# SiLPA_HE.net
KiCad netlist of a schematic drawn in Altium Designer
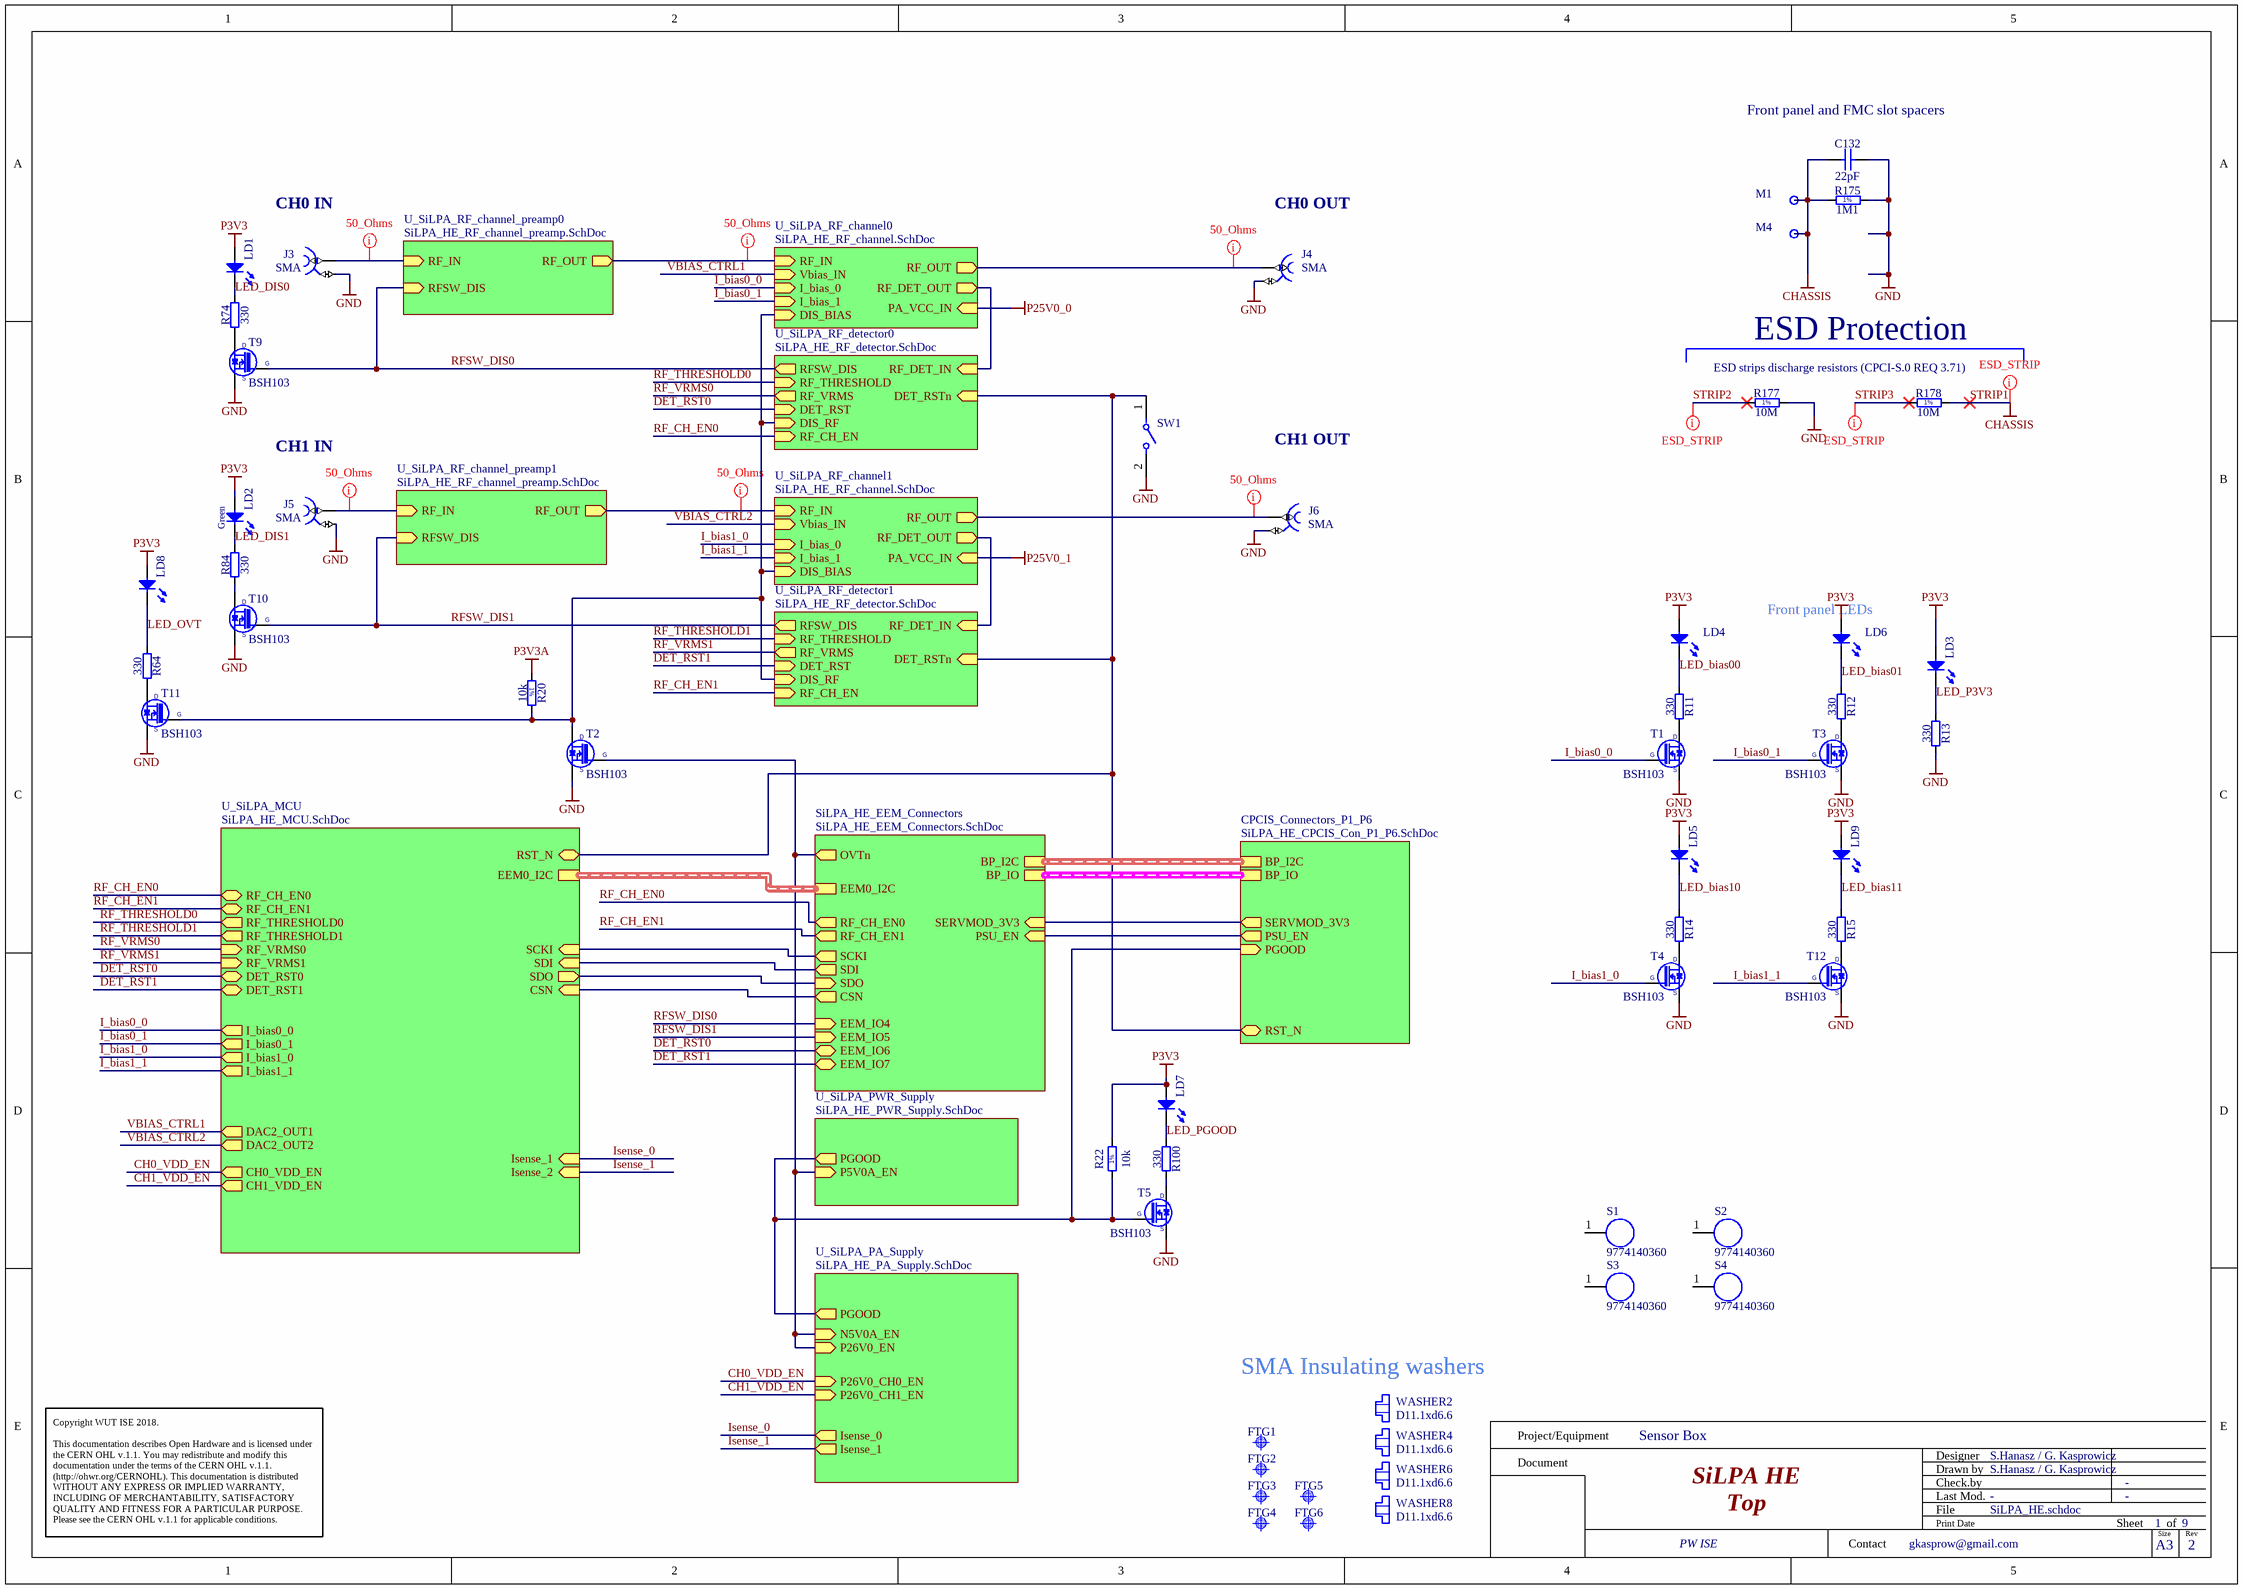
[diagram p0: SiLPA_HE.schdoc]

(export (version "E")
  (design (tool "Eeschema 10.0.6"))
  (components
    (comp (ref "C132")
      (value "22pF")
      (footprint "CAPC1005X55N")
      (description "Non-polarised capacitor")
      (fields
        (field (name "PART NUMBER") "CC0402_22PF_50V_5%_C0G")
        (field (name "VOLTAGE") "50V")
        (field (name "AUTHOR") "CERN DEM JLC")
      )
      (libsource (lib "Capacitors") (part "Capacitor - non polarized"))
    )
    (comp (ref "FTG1")
      (value "Use only in PCB")
      (footprint "FIDUCIAL_TOP_C100-200")
      (description "Fiducial Target")
      (fields (field (name "PART NUMBER") "FIDUCIAL_TARGET_C100-200") (field (name "AUTHOR") "CERN DEM JLC"))
      (libsource (lib "Eletro-mechanical") (part "Fiducial Target"))
    )
    (comp (ref "FTG2")
      (value "Use only in PCB")
      (footprint "FIDUCIAL_TOP_S100-200")
      (description "Fiducial Target")
      (fields (field (name "PART NUMBER") "FIDUCIAL_TARGET_S100-200") (field (name "AUTHOR") "CERN DEM JLC"))
      (libsource (lib "Eletro-mechanical") (part "Fiducial Target"))
    )
    (comp (ref "FTG3")
      (value "Use only in PCB")
      (footprint "FIDUCIAL_TOP_S100-200")
      (description "Fiducial Target")
      (fields (field (name "PART NUMBER") "FIDUCIAL_TARGET_S100-200") (field (name "AUTHOR") "CERN DEM JLC"))
      (libsource (lib "Eletro-mechanical") (part "Fiducial Target"))
    )
    (comp (ref "FTG4")
      (value "Use only in PCB")
      (footprint "FIDUCIAL_TOP_S100-200")
      (description "Fiducial Target")
      (fields (field (name "PART NUMBER") "FIDUCIAL_TARGET_S100-200") (field (name "AUTHOR") "CERN DEM JLC"))
      (libsource (lib "Eletro-mechanical") (part "Fiducial Target"))
    )
    (comp (ref "FTG5")
      (value "Use only in PCB")
      (footprint "FIDUCIAL_TOP_S100-200")
      (description "Fiducial Target")
      (fields (field (name "PART NUMBER") "FIDUCIAL_TARGET_S100-200") (field (name "AUTHOR") "CERN DEM JLC"))
      (libsource (lib "Eletro-mechanical") (part "Fiducial Target"))
    )
    (comp (ref "FTG6")
      (value "Use only in PCB")
      (footprint "FIDUCIAL_TOP_S100-200")
      (description "Fiducial Target")
      (fields (field (name "PART NUMBER") "FIDUCIAL_TARGET_S100-200") (field (name "AUTHOR") "CERN DEM JLC"))
      (libsource (lib "Eletro-mechanical") (part "Fiducial Target"))
    )
    (comp (ref "J3")
      (value "SMA")
      (footprint "SiLPA:DELOCK_65848")
      (description "50 Ohm Through Hole SMA Right Angle PCB Jack")
      (fields
        (field (name "PART NUMBER") "DELOCK_65848")
        (field (name "MANUFACTURER") "DELOCK")
        (field (name "AUTHOR") "GK")
      )
      (libsource (lib "") (part "DELOCK_65848_1"))
    )
    (comp (ref "J4")
      (value "SMA")
      (footprint "SiLPA:DELOCK_65848")
      (description "50 Ohm Through Hole SMA Right Angle PCB Jack")
      (fields
        (field (name "PART NUMBER") "DELOCK_65848")
        (field (name "MANUFACTURER") "DELOCK")
        (field (name "AUTHOR") "GK")
      )
      (libsource (lib "SiLPA") (part "DELOCK_65848"))
    )
    (comp (ref "J5")
      (value "SMA")
      (footprint "SiLPA:DELOCK_65848")
      (description "50 Ohm Through Hole SMA Right Angle PCB Jack")
      (fields
        (field (name "PART NUMBER") "DELOCK_65848")
        (field (name "MANUFACTURER") "DELOCK")
        (field (name "AUTHOR") "GK")
      )
      (libsource (lib "") (part "DELOCK_65848_1"))
    )
    (comp (ref "J6")
      (value "SMA")
      (footprint "SiLPA:DELOCK_65848")
      (description "50 Ohm Through Hole SMA Right Angle PCB Jack")
      (fields
        (field (name "PART NUMBER") "DELOCK_65848")
        (field (name "MANUFACTURER") "DELOCK")
        (field (name "AUTHOR") "GK")
      )
      (libsource (lib "SiLPA") (part "DELOCK_65848"))
    )
    (comp (ref "LD1")
      (value "~")
      (footprint "LED_AVAGO_HSMC-C120")
      (description "LED Red 1C 2A")
      (fields
        (field (name "PART NUMBER") "LED_AVAGO_HSMC-C120")
        (field (name "MANUFACTURER") "AVAGO TECHNOLOGIES")
        (field (name "AUTHOR") "CERN DEM JMW")
      )
      (libsource (lib "SiLPA_own") (part "LED Red 1C 2A"))
    )
    (comp (ref "LD2")
      (value "Green")
      (footprint "LED_AVAGO_HSME-C120")
      (description "LED Green 1C 2A")
      (fields
        (field (name "PART NUMBER") "LED_AVAGO_HSME-C120")
        (field (name "MANUFACTURER") "AVAGO TECHNOLOGIES")
        (field (name "AUTHOR") "CERN DEM JMW")
      )
      (libsource (lib "SiLPA_own") (part "LED_AVAGO_HSME-C120"))
    )
    (comp (ref "LD3")
      (value "~")
      (footprint "LED_AVAGO_HSME-C120")
      (description "LED Green 1C 2A")
      (fields
        (field (name "PART NUMBER") "LED_AVAGO_HSME-C120")
        (field (name "MANUFACTURER") "AVAGO TECHNOLOGIES")
        (field (name "AUTHOR") "CERN DEM JMW")
      )
      (libsource (lib "SiLPA_own") (part "LED Green 1C 2A"))
    )
    (comp (ref "LD4")
      (value "~")
      (footprint "LED_AVAGO_HSME-C120")
      (description "LED Green 1C 2A")
      (fields
        (field (name "PART NUMBER") "LED_AVAGO_HSME-C120")
        (field (name "MANUFACTURER") "AVAGO TECHNOLOGIES")
        (field (name "AUTHOR") "CERN DEM JMW")
      )
      (libsource (lib "SiLPA_own") (part "LED Green 1C 2A"))
    )
    (comp (ref "LD5")
      (value "~")
      (footprint "LED_AVAGO_HSME-C120")
      (description "LED Green 1C 2A")
      (fields
        (field (name "PART NUMBER") "LED_AVAGO_HSME-C120")
        (field (name "MANUFACTURER") "AVAGO TECHNOLOGIES")
        (field (name "AUTHOR") "CERN DEM JMW")
      )
      (libsource (lib "SiLPA_own") (part "LED Green 1C 2A"))
    )
    (comp (ref "LD6")
      (value "~")
      (footprint "LED_AVAGO_HSME-C120")
      (description "LED Green 1C 2A")
      (fields
        (field (name "PART NUMBER") "LED_AVAGO_HSME-C120")
        (field (name "MANUFACTURER") "AVAGO TECHNOLOGIES")
        (field (name "AUTHOR") "CERN DEM JMW")
      )
      (libsource (lib "SiLPA_own") (part "LED Green 1C 2A"))
    )
    (comp (ref "LD7")
      (value "~")
      (footprint "LED_AVAGO_HSME-C120")
      (description "LED Green 1C 2A")
      (fields
        (field (name "PART NUMBER") "LED_AVAGO_HSME-C120")
        (field (name "MANUFACTURER") "AVAGO TECHNOLOGIES")
        (field (name "AUTHOR") "CERN DEM JMW")
      )
      (libsource (lib "SiLPA_own") (part "LED Green 1C 2A"))
    )
    (comp (ref "LD8")
      (value "~")
      (footprint "LED_AVAGO_HSMC-C120")
      (description "LED Red 1C 2A")
      (fields
        (field (name "PART NUMBER") "LED_AVAGO_HSMC-C120")
        (field (name "MANUFACTURER") "AVAGO TECHNOLOGIES")
        (field (name "AUTHOR") "CERN DEM JMW")
      )
      (libsource (lib "SiLPA_own") (part "LED Red 1C 2A"))
    )
    (comp (ref "LD9")
      (value "~")
      (footprint "LED_AVAGO_HSME-C120")
      (description "LED Green 1C 2A")
      (fields
        (field (name "PART NUMBER") "LED_AVAGO_HSME-C120")
        (field (name "MANUFACTURER") "AVAGO TECHNOLOGIES")
        (field (name "AUTHOR") "CERN DEM JMW")
      )
      (libsource (lib "SiLPA_own") (part "LED Green 1C 2A"))
    )
    (comp (ref "M1")
      (value "Plated Hole")
      (footprint "MTG300_600")
      (description "Single Terminal Socket")
      (fields (field (name "PART NUMBER") "PLATED_HOLE3.0_PAD6.0") (field (name "AUTHOR") "CERN DEM JLC"))
      (libsource (lib "Eletro-mechanical") (part "Single Terminal Socket"))
    )
    (comp (ref "M4")
      (value "Plated Hole")
      (footprint "MTG300_600")
      (description "Single Terminal Socket")
      (fields (field (name "PART NUMBER") "PLATED_HOLE3.0_PAD6.0") (field (name "AUTHOR") "CERN DEM JLC"))
      (libsource (lib "Eletro-mechanical") (part "Single Terminal Socket"))
    )
    (comp (ref "R11")
      (value "330")
      (footprint "RESC1005X40N")
      (description "Resistor - 1%")
      (fields
        (field (name "PART NUMBER") "R0402_330R_1%_0.0625W_100PPM")
        (field (name "POWER") "0.0625W")
        (field (name "AUTHOR") "CERN DEM JLC")
      )
      (libsource (lib "Resistors") (part "Resistor - 1%"))
    )
    (comp (ref "R12")
      (value "330")
      (footprint "RESC1005X40N")
      (description "Resistor - 1%")
      (fields
        (field (name "PART NUMBER") "R0402_330R_1%_0.0625W_100PPM")
        (field (name "POWER") "0.0625W")
        (field (name "AUTHOR") "CERN DEM JLC")
      )
      (libsource (lib "Resistors") (part "Resistor - 1%"))
    )
    (comp (ref "R13")
      (value "330")
      (footprint "RESC1005X40N")
      (description "Resistor - 1%")
      (fields
        (field (name "PART NUMBER") "R0402_330R_1%_0.0625W_100PPM")
        (field (name "POWER") "0.0625W")
        (field (name "AUTHOR") "CERN DEM JLC")
      )
      (libsource (lib "Resistors") (part "Resistor - 1%"))
    )
    (comp (ref "R14")
      (value "330")
      (footprint "RESC1005X40N")
      (description "Resistor - 1%")
      (fields
        (field (name "PART NUMBER") "R0402_330R_1%_0.0625W_100PPM")
        (field (name "POWER") "0.0625W")
        (field (name "AUTHOR") "CERN DEM JLC")
      )
      (libsource (lib "Resistors") (part "Resistor - 1%"))
    )
    (comp (ref "R15")
      (value "330")
      (footprint "RESC1005X40N")
      (description "Resistor - 1%")
      (fields
        (field (name "PART NUMBER") "R0402_330R_1%_0.0625W_100PPM")
        (field (name "POWER") "0.0625W")
        (field (name "AUTHOR") "CERN DEM JLC")
      )
      (libsource (lib "Resistors") (part "Resistor - 1%"))
    )
    (comp (ref "R20")
      (value "10k")
      (footprint "RESC1005X40N")
      (description "Resistor - 1%")
      (fields
        (field (name "PART NUMBER") "R0402_10K_1%_0.0625W_100PPM")
        (field (name "POWER") "0.0625W")
        (field (name "AUTHOR") "CERN DEM JLC")
      )
      (libsource (lib "Resistors") (part "Resistor - 1%"))
    )
    (comp (ref "R22")
      (value "10k")
      (footprint "RESC1005X40N")
      (description "Resistor - 1%")
      (fields
        (field (name "PART NUMBER") "R0402_10K_1%_0.0625W_100PPM")
        (field (name "POWER") "0.0625W")
        (field (name "AUTHOR") "CERN DEM JLC")
      )
      (libsource (lib "EEM_FMC_Carrier") (part "R0402_10K_1%_0.0625W_100PPM"))
    )
    (comp (ref "R64")
      (value "330")
      (footprint "RESC1005X40N")
      (description "Resistor - 1%")
      (fields
        (field (name "PART NUMBER") "R0402_330R_1%_0.0625W_100PPM")
        (field (name "POWER") "0.0625W")
        (field (name "AUTHOR") "CERN DEM JLC")
      )
      (libsource (lib "Resistors") (part "Resistor - 1%"))
    )
    (comp (ref "R74")
      (value "330")
      (footprint "RESC1005X40N")
      (description "Resistor - 1%")
      (fields
        (field (name "PART NUMBER") "R0402_330R_1%_0.0625W_100PPM")
        (field (name "POWER") "0.0625W")
        (field (name "AUTHOR") "CERN DEM JLC")
      )
      (libsource (lib "Resistors") (part "Resistor - 1%"))
    )
    (comp (ref "R84")
      (value "330")
      (footprint "RESC1005X40N")
      (description "Resistor - 1%")
      (fields
        (field (name "PART NUMBER") "R0402_330R_1%_0.0625W_100PPM")
        (field (name "POWER") "0.0625W")
        (field (name "AUTHOR") "CERN DEM JLC")
      )
      (libsource (lib "Resistors") (part "Resistor - 1%"))
    )
    (comp (ref "R100")
      (value "330")
      (footprint "RESC1005X40N")
      (description "Resistor - 1%")
      (fields
        (field (name "PART NUMBER") "R0402_330R_1%_0.0625W_100PPM")
        (field (name "POWER") "0.0625W")
        (field (name "AUTHOR") "CERN DEM JLC")
      )
      (libsource (lib "Resistors") (part "Resistor - 1%"))
    )
    (comp (ref "R175")
      (value "1M1")
      (footprint "RESC2012X60N")
      (description "Resistor - 1%")
      (fields
        (field (name "PART NUMBER") "R0805_1M1_1%_0.125W_100PPM")
        (field (name "POWER") "0.125W")
        (field (name "AUTHOR") "CERN DEM JLC")
      )
      (libsource (lib "") (part "Resistor - 1%_1"))
    )
    (comp (ref "R177")
      (value "10M")
      (footprint "RESC2113X55N")
      (description "Resistor - 1%")
      (fields
        (field (name "PART NUMBER") "R0805_10M_1%_0.125W_100PPM_VISHAY_CRCW e3")
        (field (name "POWER") "0.125W")
        (field (name "AUTHOR") "CERN DEM BC")
      )
      (libsource (lib "") (part "Resistor - 1%_1"))
    )
    (comp (ref "R178")
      (value "10M")
      (footprint "RESC2113X55N")
      (description "Resistor - 1%")
      (fields
        (field (name "PART NUMBER") "R0805_10M_1%_0.125W_100PPM_VISHAY_CRCW e3")
        (field (name "POWER") "0.125W")
        (field (name "AUTHOR") "CERN DEM BC")
      )
      (libsource (lib "") (part "Resistor - 1%_1"))
    )
    (comp (ref "S1")
      (value "9774140360")
      (footprint "9774140360")
      (description "WA-SMSI SMD Steel Spacer with internal Thread")
      (fields (field (name "MANUFACTURER") "Wurth Elektronik") (field (name "CREATED BY") "Baojun Chen"))
      (libsource (lib "Altium_SMSI_SMT_STEEL_SPACER_M2_5_THREAD_INTERNAL_rev15a") (part "WA-SMSI,  9774140360"))
    )
    (comp (ref "S2")
      (value "9774140360")
      (footprint "9774140360")
      (description "WA-SMSI SMD Steel Spacer with internal Thread")
      (fields (field (name "MANUFACTURER") "Wurth Elektronik") (field (name "CREATED BY") "Baojun Chen"))
      (libsource (lib "Altium_SMSI_SMT_STEEL_SPACER_M2_5_THREAD_INTERNAL_rev15a") (part "WA-SMSI,  9774140360"))
    )
    (comp (ref "S3")
      (value "9774140360")
      (footprint "9774140360")
      (description "WA-SMSI SMD Steel Spacer with internal Thread")
      (fields (field (name "MANUFACTURER") "Wurth Elektronik") (field (name "CREATED BY") "Baojun Chen"))
      (libsource (lib "Altium_SMSI_SMT_STEEL_SPACER_M2_5_THREAD_INTERNAL_rev15a") (part "WA-SMSI,  9774140360"))
    )
    (comp (ref "S4")
      (value "9774140360")
      (footprint "9774140360")
      (description "WA-SMSI SMD Steel Spacer with internal Thread")
      (fields (field (name "MANUFACTURER") "Wurth Elektronik") (field (name "CREATED BY") "Baojun Chen"))
      (libsource (lib "Altium_SMSI_SMT_STEEL_SPACER_M2_5_THREAD_INTERNAL_rev15a") (part "WA-SMSI,  9774140360"))
    )
    (comp (ref "SW1")
      (value "~")
      (footprint "FP-B3U-3000PM-MFG")
      (description "SWITCH TACTILE SPST-NO 0.05A 12V")
      (libsource (lib "SiLPA_own") (part "bb27bde45df87f1f469753f287ef5ae"))
    )
    (comp (ref "T1")
      (value "BSH103")
      (footprint "SOT95P230X110-3N")
      (description "N-CHANNEL MOSFET WITH DIODE")
      (fields (field (name "MANUFACTURER") "NEXPERIA") (field (name "AUTHOR") "CERN DEM JLC"))
      (libsource (lib "ICs And Semiconductors") (part "N-MOSFET-D 1G 2S 3D"))
    )
    (comp (ref "T2")
      (value "BSH103")
      (footprint "SOT95P230X110-3N")
      (description "N-CHANNEL MOSFET WITH DIODE")
      (fields (field (name "MANUFACTURER") "NEXPERIA") (field (name "AUTHOR") "CERN DEM JLC"))
      (libsource (lib "") (part "N-MOSFET-D 1G 2S 3D_1"))
    )
    (comp (ref "T3")
      (value "BSH103")
      (footprint "SOT95P230X110-3N")
      (description "N-CHANNEL MOSFET WITH DIODE")
      (fields (field (name "MANUFACTURER") "NEXPERIA") (field (name "AUTHOR") "CERN DEM JLC"))
      (libsource (lib "ICs And Semiconductors") (part "N-MOSFET-D 1G 2S 3D"))
    )
    (comp (ref "T4")
      (value "BSH103")
      (footprint "SOT95P230X110-3N")
      (description "N-CHANNEL MOSFET WITH DIODE")
      (fields (field (name "MANUFACTURER") "NEXPERIA") (field (name "AUTHOR") "CERN DEM JLC"))
      (libsource (lib "ICs And Semiconductors") (part "N-MOSFET-D 1G 2S 3D"))
    )
    (comp (ref "T5")
      (value "BSH103")
      (footprint "SOT95P230X110-3N")
      (description "N-CHANNEL MOSFET WITH DIODE")
      (fields (field (name "MANUFACTURER") "NEXPERIA") (field (name "AUTHOR") "CERN DEM JLC"))
      (libsource (lib "ICs And Semiconductors") (part "N-MOSFET-D 1G 2S 3D"))
    )
    (comp (ref "T9")
      (value "BSH103")
      (footprint "SOT95P230X110-3N")
      (description "N-CHANNEL MOSFET WITH DIODE")
      (fields (field (name "MANUFACTURER") "NEXPERIA") (field (name "AUTHOR") "CERN DEM JLC"))
      (libsource (lib "") (part "N-MOSFET-D 1G 2S 3D_1"))
    )
    (comp (ref "T10")
      (value "BSH103")
      (footprint "SOT95P230X110-3N")
      (description "N-CHANNEL MOSFET WITH DIODE")
      (fields (field (name "MANUFACTURER") "NEXPERIA") (field (name "AUTHOR") "CERN DEM JLC"))
      (libsource (lib "") (part "N-MOSFET-D 1G 2S 3D_1"))
    )
    (comp (ref "T11")
      (value "BSH103")
      (footprint "SOT95P230X110-3N")
      (description "N-CHANNEL MOSFET WITH DIODE")
      (fields (field (name "MANUFACTURER") "NEXPERIA") (field (name "AUTHOR") "CERN DEM JLC"))
      (libsource (lib "") (part "N-MOSFET-D 1G 2S 3D_1"))
    )
    (comp (ref "T12")
      (value "BSH103")
      (footprint "SOT95P230X110-3N")
      (description "N-CHANNEL MOSFET WITH DIODE")
      (fields (field (name "MANUFACTURER") "NEXPERIA") (field (name "AUTHOR") "CERN DEM JLC"))
      (libsource (lib "ICs And Semiconductors") (part "N-MOSFET-D 1G 2S 3D"))
    )
    (comp (ref "WASHER2")
      (value "D11.1xd6.6")
      (footprint "Keystone_7687")
      (description "SMA_Shoulder Washer")
      (fields (field (name "PART NUMBER") "custom 3D") (field (name "AUTHOR") "GK"))
      (libsource (lib "SiLPA_own") (part "Keystone_7687"))
    )
    (comp (ref "WASHER4")
      (value "D11.1xd6.6")
      (footprint "Keystone_7687")
      (description "SMA_Shoulder Washer")
      (fields (field (name "PART NUMBER") "custom 3D") (field (name "AUTHOR") "GK"))
      (libsource (lib "SiLPA_own") (part "Keystone_7687"))
    )
    (comp (ref "WASHER6")
      (value "D11.1xd6.6")
      (footprint "Keystone_7687")
      (description "SMA_Shoulder Washer")
      (fields (field (name "PART NUMBER") "custom 3D") (field (name "AUTHOR") "GK"))
      (libsource (lib "SiLPA_own") (part "Keystone_7687"))
    )
    (comp (ref "WASHER8")
      (value "D11.1xd6.6")
      (footprint "Keystone_7687")
      (description "SMA_Shoulder Washer")
      (fields (field (name "PART NUMBER") "custom 3D") (field (name "AUTHOR") "GK"))
      (libsource (lib "SiLPA_own") (part "Keystone_7687"))
    )
  )
  (nets
    (net (code "8") (name "/DET_RSTn") (class "Default")
      (node (ref "SW1") (pin "1") (pinfunction "1_1") (pintype "passive"))
    )
    (net (code "9") (name "/DIS_BIAS") (class "Default")
      (node (ref "R20") (pin "2") (pinfunction "2_2") (pintype "passive"))
      (node (ref "T11") (pin "1") (pinfunction "G_1") (pintype "passive"))
      (node (ref "T2") (pin "3") (pinfunction "D_3") (pintype "passive"))
    )
    (net (code "11") (name "/I_bias0_0") (class "Default")
      (node (ref "T1") (pin "1") (pinfunction "G_1") (pintype "passive"))
    )
    (net (code "12") (name "/I_bias0_1") (class "Default")
      (node (ref "T3") (pin "1") (pinfunction "G_1") (pintype "passive"))
    )
    (net (code "13") (name "/I_bias1_0") (class "Default")
      (node (ref "T4") (pin "1") (pinfunction "G_1") (pintype "passive"))
    )
    (net (code "14") (name "/I_bias1_1") (class "Default")
      (node (ref "T12") (pin "1") (pinfunction "G_1") (pintype "passive"))
    )
    (net (code "17") (name "/LED_DIS0") (class "Default")
      (node (ref "LD1") (pin "1") (pinfunction "C_1") (pintype "passive"))
      (node (ref "R74") (pin "1") (pinfunction "1_1") (pintype "passive"))
    )
    (net (code "18") (name "/LED_DIS1") (class "Default")
      (node (ref "LD2") (pin "1") (pinfunction "C_1") (pintype "passive"))
      (node (ref "R84") (pin "1") (pinfunction "1_1") (pintype "passive"))
    )
    (net (code "19") (name "/LED_OVT") (class "Default")
      (node (ref "LD8") (pin "1") (pinfunction "C_1") (pintype "passive"))
      (node (ref "R64") (pin "1") (pinfunction "1_1") (pintype "passive"))
    )
    (net (code "20") (name "/LED_P3V3") (class "Default")
      (node (ref "LD3") (pin "1") (pinfunction "C_1") (pintype "passive"))
      (node (ref "R13") (pin "1") (pinfunction "1_1") (pintype "passive"))
    )
    (net (code "21") (name "/LED_PGOOD") (class "Default")
      (node (ref "LD7") (pin "1") (pinfunction "C_1") (pintype "passive"))
      (node (ref "R100") (pin "1") (pinfunction "1_1") (pintype "passive"))
    )
    (net (code "22") (name "/LED_bias00") (class "Default")
      (node (ref "LD4") (pin "1") (pinfunction "C_1") (pintype "passive"))
      (node (ref "R11") (pin "1") (pinfunction "1_1") (pintype "passive"))
    )
    (net (code "23") (name "/LED_bias01") (class "Default")
      (node (ref "LD6") (pin "1") (pinfunction "C_1") (pintype "passive"))
      (node (ref "R12") (pin "1") (pinfunction "1_1") (pintype "passive"))
    )
    (net (code "24") (name "/LED_bias10") (class "Default")
      (node (ref "LD5") (pin "1") (pinfunction "C_1") (pintype "passive"))
      (node (ref "R14") (pin "1") (pinfunction "1_1") (pintype "passive"))
    )
    (net (code "25") (name "/LED_bias11") (class "Default")
      (node (ref "LD9") (pin "1") (pinfunction "C_1") (pintype "passive"))
      (node (ref "R15") (pin "1") (pinfunction "1_1") (pintype "passive"))
    )
    (net (code "26") (name "/OVTn") (class "Default")
      (node (ref "T2") (pin "1") (pinfunction "G_1") (pintype "passive"))
    )
    (net (code "27") (name "/PGOOD") (class "Default")
      (node (ref "R22") (pin "1") (pinfunction "1_1") (pintype "passive"))
      (node (ref "T5") (pin "1") (pinfunction "G_1") (pintype "passive"))
    )
    (net (code "29") (name "/RFSW_DIS0") (class "Default")
      (node (ref "T9") (pin "1") (pinfunction "G_1") (pintype "passive"))
    )
    (net (code "30") (name "/RFSW_DIS1") (class "Default")
      (node (ref "T10") (pin "1") (pinfunction "G_1") (pintype "passive"))
    )
    (net (code "35") (name "/RF_IN") (class "Default")
      (node (ref "J5") (pin "1") (pinfunction "1_1") (pintype "bidirectional"))
    )
    (net (code "36") (name "/RF_IN_1") (class "Default")
      (node (ref "J3") (pin "1") (pinfunction "1_1") (pintype "bidirectional"))
    )
    (net (code "38") (name "/RF_OUT_1") (class "Default")
      (node (ref "J4") (pin "1") (pinfunction "1_1") (pintype "bidirectional"))
    )
    (net (code "39") (name "/RF_OUT_2") (class "Default")
      (node (ref "J6") (pin "1") (pinfunction "1_1") (pintype "bidirectional"))
    )
    (net (code "50") (name "/STRIP2") (class "Default")
      (node (ref "R177") (pin "1") (pinfunction "1_1") (pintype "passive+no_connect"))
    )
    (net (code "51") (name "/STRIP3") (class "Default")
      (node (ref "R178") (pin "1") (pinfunction "1_1") (pintype "passive+no_connect"))
    )
    (net (code "54") (name "CHASSIS") (class "Default")
      (node (ref "C132") (pin "1") (pinfunction "1_1") (pintype "passive"))
      (node (ref "M1") (pin "1") (pinfunction "1_1") (pintype "bidirectional"))
      (node (ref "M4") (pin "1") (pinfunction "1_1") (pintype "bidirectional"))
      (node (ref "R175") (pin "1") (pinfunction "1_1") (pintype "passive"))
      (node (ref "R178") (pin "2") (pinfunction "2_2") (pintype "passive"))
    )
    (net (code "55") (name "GND") (class "Default")
      (node (ref "C132") (pin "2") (pinfunction "2_2") (pintype "passive"))
      (node (ref "J3") (pin "2") (pinfunction "2_2") (pintype "bidirectional"))
      (node (ref "J4") (pin "2") (pinfunction "2_2") (pintype "bidirectional"))
      (node (ref "J5") (pin "2") (pinfunction "2_2") (pintype "bidirectional"))
      (node (ref "J6") (pin "2") (pinfunction "2_2") (pintype "bidirectional"))
      (node (ref "R13") (pin "2") (pinfunction "2_2") (pintype "passive"))
      (node (ref "R175") (pin "2") (pinfunction "2_2") (pintype "passive"))
      (node (ref "R177") (pin "2") (pinfunction "2_2") (pintype "passive"))
      (node (ref "SW1") (pin "2") (pinfunction "2_2") (pintype "passive"))
      (node (ref "T1") (pin "2") (pinfunction "S_2") (pintype "passive"))
      (node (ref "T10") (pin "2") (pinfunction "S_2") (pintype "passive"))
      (node (ref "T11") (pin "2") (pinfunction "S_2") (pintype "passive"))
      (node (ref "T12") (pin "2") (pinfunction "S_2") (pintype "passive"))
      (node (ref "T2") (pin "2") (pinfunction "S_2") (pintype "passive"))
      (node (ref "T3") (pin "2") (pinfunction "S_2") (pintype "passive"))
      (node (ref "T4") (pin "2") (pinfunction "S_2") (pintype "passive"))
      (node (ref "T5") (pin "2") (pinfunction "S_2") (pintype "passive"))
      (node (ref "T9") (pin "2") (pinfunction "S_2") (pintype "passive"))
    )
    (net (code "56") (name "Net-(T1-D)") (class "Default")
      (node (ref "R11") (pin "2") (pinfunction "2_2") (pintype "passive"))
      (node (ref "T1") (pin "3") (pinfunction "D_3") (pintype "passive"))
    )
    (net (code "57") (name "Net-(T3-D)") (class "Default")
      (node (ref "R12") (pin "2") (pinfunction "2_2") (pintype "passive"))
      (node (ref "T3") (pin "3") (pinfunction "D_3") (pintype "passive"))
    )
    (net (code "58") (name "Net-(T4-D)") (class "Default")
      (node (ref "R14") (pin "2") (pinfunction "2_2") (pintype "passive"))
      (node (ref "T4") (pin "3") (pinfunction "D_3") (pintype "passive"))
    )
    (net (code "59") (name "Net-(T5-D)") (class "Default")
      (node (ref "R100") (pin "2") (pinfunction "2_2") (pintype "passive"))
      (node (ref "T5") (pin "3") (pinfunction "D_3") (pintype "passive"))
    )
    (net (code "60") (name "Net-(T9-D)") (class "Default")
      (node (ref "R74") (pin "2") (pinfunction "2_2") (pintype "passive"))
      (node (ref "T9") (pin "3") (pinfunction "D_3") (pintype "passive"))
    )
    (net (code "61") (name "Net-(T10-D)") (class "Default")
      (node (ref "R84") (pin "2") (pinfunction "2_2") (pintype "passive"))
      (node (ref "T10") (pin "3") (pinfunction "D_3") (pintype "passive"))
    )
    (net (code "62") (name "Net-(T11-D)") (class "Default")
      (node (ref "R64") (pin "2") (pinfunction "2_2") (pintype "passive"))
      (node (ref "T11") (pin "3") (pinfunction "D_3") (pintype "passive"))
    )
    (net (code "63") (name "Net-(T12-D)") (class "Default")
      (node (ref "R15") (pin "2") (pinfunction "2_2") (pintype "passive"))
      (node (ref "T12") (pin "3") (pinfunction "D_3") (pintype "passive"))
    )
    (net (code "64") (name "P3V3") (class "Default")
      (node (ref "LD1") (pin "2") (pinfunction "A_2") (pintype "passive"))
      (node (ref "LD2") (pin "2") (pinfunction "A_2") (pintype "passive"))
      (node (ref "LD3") (pin "2") (pinfunction "A_2") (pintype "passive"))
      (node (ref "LD4") (pin "2") (pinfunction "A_2") (pintype "passive"))
      (node (ref "LD5") (pin "2") (pinfunction "A_2") (pintype "passive"))
      (node (ref "LD6") (pin "2") (pinfunction "A_2") (pintype "passive"))
      (node (ref "LD7") (pin "2") (pinfunction "A_2") (pintype "passive"))
      (node (ref "LD8") (pin "2") (pinfunction "A_2") (pintype "passive"))
      (node (ref "LD9") (pin "2") (pinfunction "A_2") (pintype "passive"))
      (node (ref "R22") (pin "2") (pinfunction "2_2") (pintype "passive"))
    )
    (net (code "65") (name "P3V3A") (class "Default")
      (node (ref "R20") (pin "1") (pinfunction "1_1") (pintype "passive"))
    )
    (net (code "68") (name "unconnected-(S1-Pad1)") (class "Default")
      (node (ref "S1") (pin "1") (pinfunction "1_1") (pintype "passive"))
    )
    (net (code "69") (name "unconnected-(S2-Pad1)") (class "Default")
      (node (ref "S2") (pin "1") (pinfunction "1_1") (pintype "passive"))
    )
    (net (code "70") (name "unconnected-(S3-Pad1)") (class "Default")
      (node (ref "S3") (pin "1") (pinfunction "1_1") (pintype "passive"))
    )
    (net (code "71") (name "unconnected-(S4-Pad1)") (class "Default")
      (node (ref "S4") (pin "1") (pinfunction "1_1") (pintype "passive"))
    )
  )
)
